# FieldsPanelWire.net
KiCad netlist of a schematic drawn in EAGLE
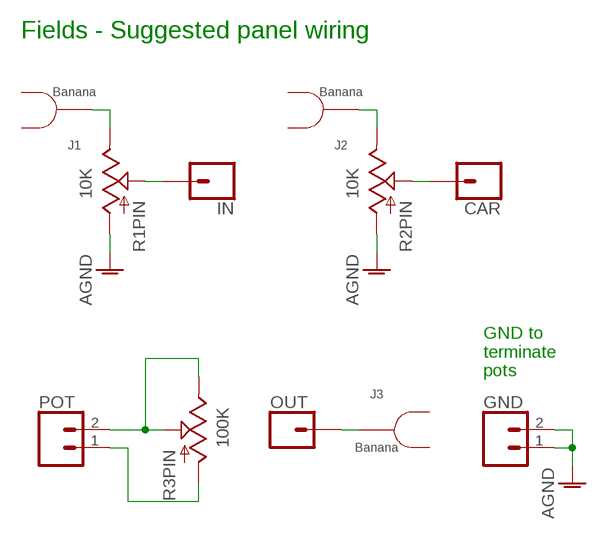
[diagram p0: schematic, sheet 1]

(export (version "E")
  (design (tool "Eeschema 10.0.6"))
  (components
    (comp (ref "CAR")
      (value "1XWIREPAD")
      (footprint "eagle-import:1X01")
      (libsource (lib "eagle-import") (part "1XWIREPAD"))
    )
    (comp (ref "GND")
      (value "2XWIREPAD")
      (footprint "eagle-import:1X02")
      (libsource (lib "eagle-import") (part "2XWIREPAD"))
    )
    (comp (ref "IN")
      (value "1XWIREPAD")
      (footprint "eagle-import:1X01")
      (libsource (lib "eagle-import") (part "1XWIREPAD"))
    )
    (comp (ref "J1")
      (value "BANANA_SOCKET_PAD")
      (footprint "eagle-import:BANANA_PCB_PAD")
      (libsource (lib "eagle-import") (part "BANANA_SOCKET_PAD"))
    )
    (comp (ref "J2")
      (value "BANANA_SOCKET_PAD")
      (footprint "eagle-import:BANANA_PCB_PAD")
      (libsource (lib "eagle-import") (part "BANANA_SOCKET_PAD"))
    )
    (comp (ref "J3")
      (value "BANANA_SOCKET_PAD")
      (footprint "eagle-import:BANANA_PCB_PAD")
      (libsource (lib "eagle-import") (part "BANANA_SOCKET_PAD"))
    )
    (comp (ref "OUT")
      (value "1XWIREPAD")
      (footprint "eagle-import:1X01")
      (libsource (lib "eagle-import") (part "1XWIREPAD"))
    )
    (comp (ref "POT")
      (value "2XWIREPAD")
      (footprint "eagle-import:1X02")
      (libsource (lib "eagle-import") (part "2XWIREPAD"))
    )
    (comp (ref "R1")
      (value "10K")
      (footprint "eagle-import:ALPHA_RV09_9MMPOT")
      (libsource (lib "eagle-import") (part "POTENTIOMETER"))
    )
    (comp (ref "R2")
      (value "10K")
      (footprint "eagle-import:ALPHA_RV09_9MMPOT")
      (libsource (lib "eagle-import") (part "POTENTIOMETER"))
    )
    (comp (ref "R3")
      (value "100K")
      (footprint "eagle-import:ALPHA_RV09_9MMPOT")
      (libsource (lib "eagle-import") (part "POTENTIOMETER"))
    )
  )
  (nets
    (net (code "1") (name "AGND") (class "Default")
      (node (ref "GND") (pin "1") (pinfunction "1_1") (pintype "passive"))
      (node (ref "GND") (pin "2") (pinfunction "2_2") (pintype "passive"))
      (node (ref "R1") (pin "C1") (pinfunction "A_C1") (pintype "passive"))
      (node (ref "R2") (pin "C1") (pinfunction "A_C1") (pintype "passive"))
    )
    (net (code "2") (name "Net-(J1-P$1)") (class "Default")
      (node (ref "J1") (pin "P$2") (pinfunction "P$1_P$2") (pintype "bidirectional"))
      (node (ref "R1") (pin "C3") (pinfunction "B_C3") (pintype "passive"))
    )
    (net (code "3") (name "Net-(J2-P$1)") (class "Default")
      (node (ref "J2") (pin "P$2") (pinfunction "P$1_P$2") (pintype "bidirectional"))
      (node (ref "R2") (pin "C3") (pinfunction "B_C3") (pintype "passive"))
    )
    (net (code "4") (name "Net-(J3-P$1)") (class "Default")
      (node (ref "J3") (pin "P$2") (pinfunction "P$1_P$2") (pintype "bidirectional"))
      (node (ref "OUT") (pin "1") (pinfunction "1_1") (pintype "passive"))
    )
    (net (code "5") (name "Net-(R1B-W)") (class "Default")
      (node (ref "IN") (pin "1") (pinfunction "1_1") (pintype "passive"))
      (node (ref "R1") (pin "C2") (pinfunction "W_C2") (pintype "passive"))
    )
    (net (code "6") (name "Net-(R2B-W)") (class "Default")
      (node (ref "CAR") (pin "1") (pinfunction "1_1") (pintype "passive"))
      (node (ref "R2") (pin "C2") (pinfunction "W_C2") (pintype "passive"))
    )
    (net (code "7") (name "Net-(R3B-A)") (class "Default")
      (node (ref "POT") (pin "1") (pinfunction "1_1") (pintype "passive"))
      (node (ref "R3") (pin "C1") (pinfunction "A_C1") (pintype "passive"))
    )
    (net (code "8") (name "Net-(R3B-B)") (class "Default")
      (node (ref "POT") (pin "2") (pinfunction "2_2") (pintype "passive"))
      (node (ref "R3") (pin "C2") (pinfunction "W_C2") (pintype "passive"))
      (node (ref "R3") (pin "C3") (pinfunction "B_C3") (pintype "passive"))
    )
  )
)
